# untitled2.net
KiCad netlist of a schematic drawn in EAGLE
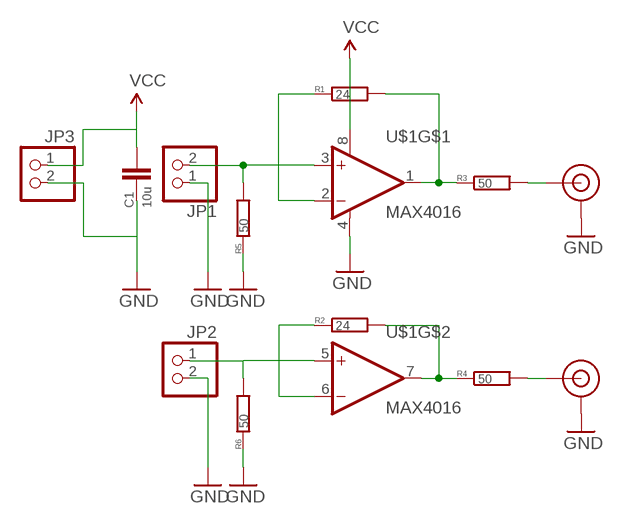
[diagram p0: schematic, sheet 1]

(export (version "E")
  (design (tool "Eeschema 10.0.6"))
  (components
    (comp (ref "C1")
      (value "10u")
      (footprint "eagle-import:C0805")
      (libsource (lib "eagle-import") (part "CC0805"))
    )
    (comp (ref "J$1")
      (value "SMA_EDGE")
      (footprint "eagle-import:SMA-EDGE")
      (libsource (lib "eagle-import") (part "SMA_EDGE"))
    )
    (comp (ref "J$2")
      (value "SMA_EDGE")
      (footprint "eagle-import:SMA-EDGE")
      (libsource (lib "eagle-import") (part "SMA_EDGE"))
    )
    (comp (ref "JP1")
      (value "PINHD-1X02_2.54")
      (footprint "eagle-import:1X02")
      (libsource (lib "eagle-import") (part "PINHD-1X02_2.54"))
    )
    (comp (ref "JP2")
      (value "PINHD-1X02_2.54")
      (footprint "eagle-import:1X02")
      (libsource (lib "eagle-import") (part "PINHD-1X02_2.54"))
    )
    (comp (ref "JP3")
      (value "PINHD-1X02_2.54")
      (footprint "eagle-import:1X02")
      (libsource (lib "eagle-import") (part "PINHD-1X02_2.54"))
    )
    (comp (ref "R1")
      (value "24")
      (footprint "eagle-import:0603")
      (libsource (lib "eagle-import") (part "R0603"))
    )
    (comp (ref "R2")
      (value "24")
      (footprint "eagle-import:0603")
      (libsource (lib "eagle-import") (part "R0603"))
    )
    (comp (ref "R3")
      (value "50")
      (footprint "eagle-import:0603")
      (libsource (lib "eagle-import") (part "R0603"))
    )
    (comp (ref "R4")
      (value "50")
      (footprint "eagle-import:0603")
      (libsource (lib "eagle-import") (part "R0603"))
    )
    (comp (ref "R5")
      (value "50")
      (footprint "eagle-import:0603")
      (libsource (lib "eagle-import") (part "R0603"))
    )
    (comp (ref "R6")
      (value "50")
      (footprint "eagle-import:0603")
      (libsource (lib "eagle-import") (part "R0603"))
    )
    (comp (ref "U$1")
      (value "MAX4016")
      (footprint "eagle-import:SO08")
      (libsource (lib "eagle-import") (part "MAX4016"))
    )
  )
  (nets
    (net (code "1") (name "GND") (class "Default")
      (node (ref "C1") (pin "2") (pinfunction "2_2") (pintype "passive"))
      (node (ref "J$1") (pin "GND@0") (pinfunction "GND_GND@0") (pintype "bidirectional"))
      (node (ref "J$1") (pin "GND@1") (pinfunction "GND_GND@1") (pintype "bidirectional"))
      (node (ref "J$1") (pin "GND@2") (pinfunction "GND_GND@2") (pintype "bidirectional"))
      (node (ref "J$1") (pin "GND@3") (pinfunction "GND_GND@3") (pintype "bidirectional"))
      (node (ref "J$2") (pin "GND@0") (pinfunction "GND_GND@0") (pintype "bidirectional"))
      (node (ref "J$2") (pin "GND@1") (pinfunction "GND_GND@1") (pintype "bidirectional"))
      (node (ref "J$2") (pin "GND@2") (pinfunction "GND_GND@2") (pintype "bidirectional"))
      (node (ref "J$2") (pin "GND@3") (pinfunction "GND_GND@3") (pintype "bidirectional"))
      (node (ref "JP1") (pin "1") (pinfunction "1_1") (pintype "passive"))
      (node (ref "JP2") (pin "2") (pinfunction "2_2") (pintype "passive"))
      (node (ref "JP3") (pin "2") (pinfunction "2_2") (pintype "passive"))
      (node (ref "R5") (pin "1") (pinfunction "1_1") (pintype "passive"))
      (node (ref "R6") (pin "1") (pinfunction "1_1") (pintype "passive"))
      (node (ref "U$1") (pin "4") (pinfunction "V-_4") (pintype "power_in"))
    )
    (net (code "2") (name "Net-(J$1-SIGNAL)") (class "Default")
      (node (ref "J$1") (pin "SIG") (pinfunction "SIGNAL_SIG") (pintype "bidirectional"))
      (node (ref "R3") (pin "2") (pinfunction "2_2") (pintype "passive"))
    )
    (net (code "3") (name "Net-(J$2-SIGNAL)") (class "Default")
      (node (ref "J$2") (pin "SIG") (pinfunction "SIGNAL_SIG") (pintype "bidirectional"))
      (node (ref "R4") (pin "2") (pinfunction "2_2") (pintype "passive"))
    )
    (net (code "4") (name "Net-(U$1A-+IN)") (class "Default")
      (node (ref "JP1") (pin "2") (pinfunction "2_2") (pintype "passive"))
      (node (ref "R5") (pin "2") (pinfunction "2_2") (pintype "passive"))
      (node (ref "U$1") (pin "3") (pinfunction "+IN_3") (pintype "input"))
    )
    (net (code "5") (name "Net-(U$1A--IN)") (class "Default")
      (node (ref "R1") (pin "1") (pinfunction "1_1") (pintype "passive"))
      (node (ref "U$1") (pin "2") (pinfunction "-IN_2") (pintype "input"))
    )
    (net (code "6") (name "Net-(U$1A-OUT)") (class "Default")
      (node (ref "R1") (pin "2") (pinfunction "2_2") (pintype "passive"))
      (node (ref "R3") (pin "1") (pinfunction "1_1") (pintype "passive"))
      (node (ref "U$1") (pin "1") (pinfunction "OUT_1") (pintype "output"))
    )
    (net (code "7") (name "Net-(U$1B-+IN)") (class "Default")
      (node (ref "JP2") (pin "1") (pinfunction "1_1") (pintype "passive"))
      (node (ref "R6") (pin "2") (pinfunction "2_2") (pintype "passive"))
      (node (ref "U$1") (pin "5") (pinfunction "+IN_5") (pintype "input"))
    )
    (net (code "8") (name "Net-(U$1B--IN)") (class "Default")
      (node (ref "R2") (pin "1") (pinfunction "1_1") (pintype "passive"))
      (node (ref "U$1") (pin "6") (pinfunction "-IN_6") (pintype "input"))
    )
    (net (code "9") (name "Net-(U$1B-OUT)") (class "Default")
      (node (ref "R2") (pin "2") (pinfunction "2_2") (pintype "passive"))
      (node (ref "R4") (pin "1") (pinfunction "1_1") (pintype "passive"))
      (node (ref "U$1") (pin "7") (pinfunction "OUT_7") (pintype "output"))
    )
    (net (code "10") (name "VCC") (class "Default")
      (node (ref "C1") (pin "1") (pinfunction "1_1") (pintype "passive"))
      (node (ref "JP3") (pin "1") (pinfunction "1_1") (pintype "passive"))
      (node (ref "U$1") (pin "8") (pinfunction "V+_8") (pintype "power_in"))
    )
  )
)
